# bhi260ap.net
KiCad netlist of a schematic drawn in Altium Designer
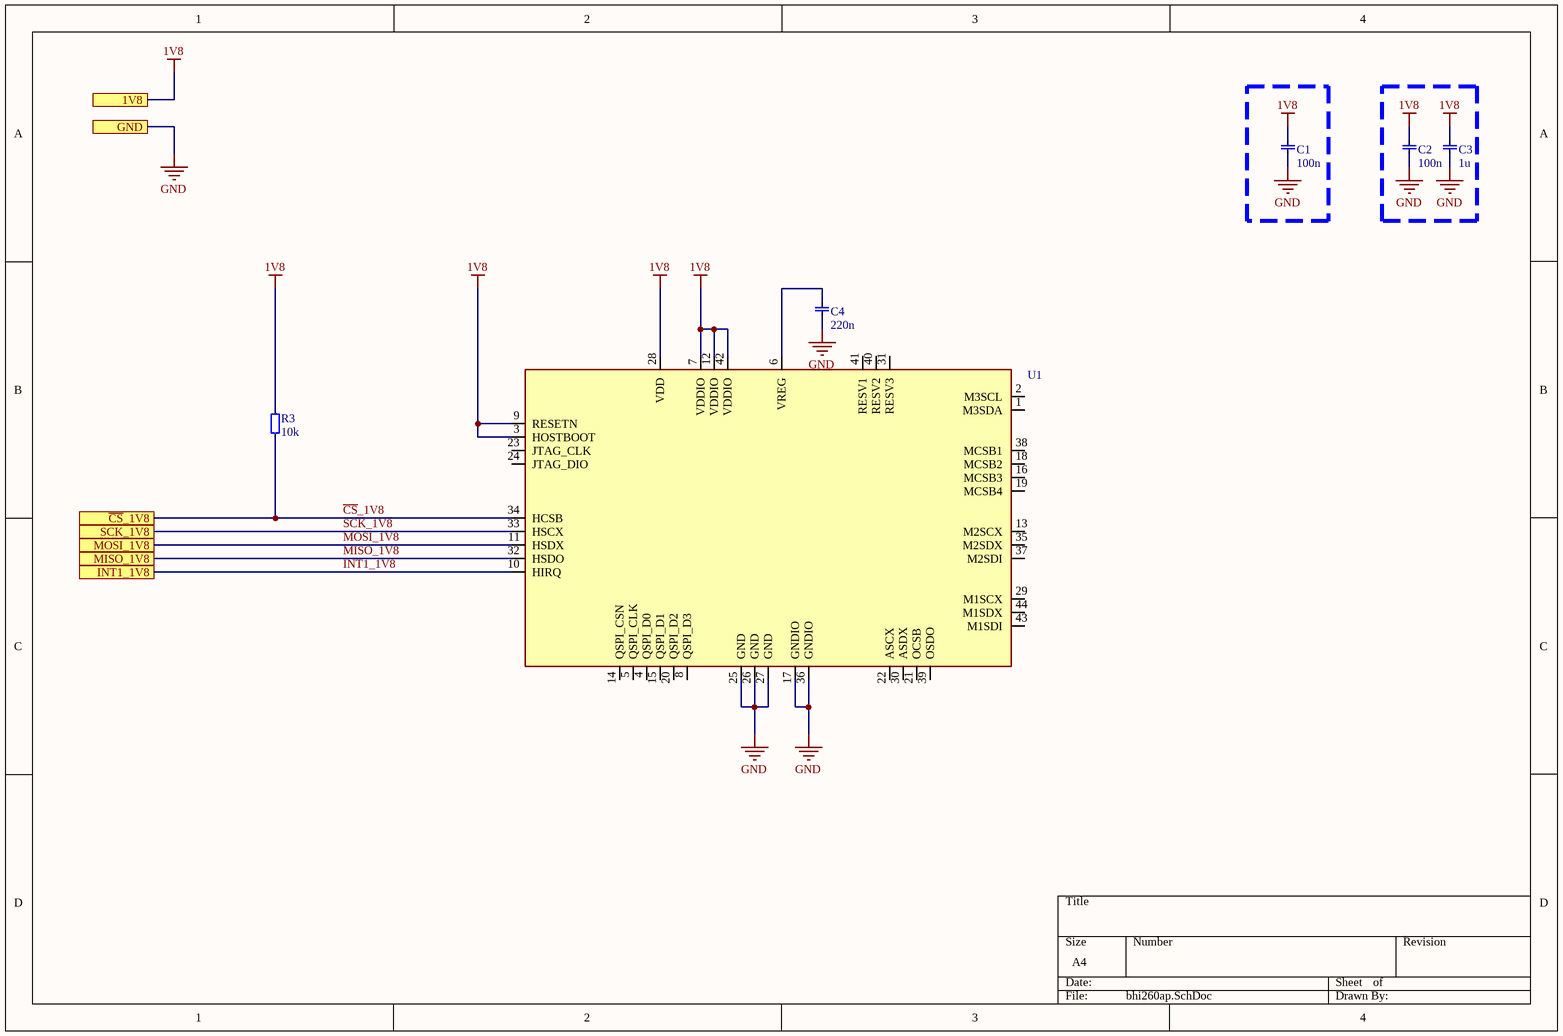
[diagram p0: bhi260ap.SchDoc]

(export (version "E")
  (design (tool "Eeschema 10.0.6"))
  (components
    (comp (ref "C1")
      (value "100n")
      (footprint "0402 CAP")
      (fields (field (name "Comment") "0402 capacitor"))
      (libsource (lib "jclib") (part "0402 capacitor"))
    )
    (comp (ref "C2")
      (value "100n")
      (footprint "0402 CAP")
      (fields (field (name "Comment") "0402 capacitor"))
      (libsource (lib "jclib") (part "0402 capacitor"))
    )
    (comp (ref "C3")
      (value "1u")
      (footprint "0402 CAP")
      (fields (field (name "Comment") "0402 capacitor"))
      (libsource (lib "jclib") (part "0402 capacitor"))
    )
    (comp (ref "C4")
      (value "220n")
      (footprint "0402 CAP")
      (fields (field (name "Comment") "0402 capacitor"))
      (libsource (lib "jclib") (part "0402 capacitor"))
    )
    (comp (ref "R3")
      (value "10k")
      (footprint "0402 res")
      (fields (field (name "Comment") "0402, resistor"))
      (libsource (lib "jclib") (part "0402, resistor"))
    )
    (comp (ref "U1")
      (value "BHI260AP")
      (footprint "44-LGA")
      (description "Self-learning AI smart sensor with integrated IMU")
      (libsource (lib "jclib") (part "BHI260AP"))
    )
  )
  (nets
    (net (code "1") (name "/INT1_1V8") (class "Default")
      (node (ref "U1") (pin "10") (pinfunction "HIRQ_10") (pintype "passive"))
    )
    (net (code "2") (name "/MISO_1V8") (class "Default")
      (node (ref "U1") (pin "32") (pinfunction "HSDO_32") (pintype "passive"))
    )
    (net (code "3") (name "/MOSI_1V8") (class "Default")
      (node (ref "U1") (pin "11") (pinfunction "HSDX_11") (pintype "passive"))
    )
    (net (code "4") (name "/SCK_1V8") (class "Default")
      (node (ref "U1") (pin "33") (pinfunction "HSCX_33") (pintype "passive"))
    )
    (net (code "5") (name "/~{CS}_1V8") (class "Default")
      (node (ref "R3") (pin "1") (pinfunction "1_1") (pintype "passive"))
      (node (ref "U1") (pin "34") (pinfunction "HCSB_34") (pintype "passive"))
    )
    (net (code "6") (name "1V8") (class "Default")
      (node (ref "C1") (pin "1") (pinfunction "1_1") (pintype "passive"))
      (node (ref "C2") (pin "1") (pinfunction "1_1") (pintype "passive"))
      (node (ref "C3") (pin "1") (pinfunction "1_1") (pintype "passive"))
      (node (ref "R3") (pin "0") (pinfunction "0_0") (pintype "passive"))
      (node (ref "U1") (pin "12") (pinfunction "VDDIO_12") (pintype "passive"))
      (node (ref "U1") (pin "28") (pinfunction "VDD_28") (pintype "passive"))
      (node (ref "U1") (pin "3") (pinfunction "HOSTBOOT_3") (pintype "passive"))
      (node (ref "U1") (pin "42") (pinfunction "VDDIO_42") (pintype "passive"))
      (node (ref "U1") (pin "7") (pinfunction "VDDIO_7") (pintype "passive"))
      (node (ref "U1") (pin "9") (pinfunction "RESETN_9") (pintype "passive"))
    )
    (net (code "7") (name "GND") (class "Default")
      (node (ref "C1") (pin "0") (pinfunction "0_0") (pintype "passive"))
      (node (ref "C2") (pin "0") (pinfunction "0_0") (pintype "passive"))
      (node (ref "C3") (pin "0") (pinfunction "0_0") (pintype "passive"))
      (node (ref "C4") (pin "0") (pinfunction "0_0") (pintype "passive"))
      (node (ref "U1") (pin "17") (pinfunction "GNDIO_17") (pintype "passive"))
      (node (ref "U1") (pin "25") (pinfunction "GND_25") (pintype "passive"))
      (node (ref "U1") (pin "26") (pinfunction "GND_26") (pintype "passive"))
      (node (ref "U1") (pin "27") (pinfunction "GND_27") (pintype "passive"))
      (node (ref "U1") (pin "36") (pinfunction "GNDIO_36") (pintype "passive"))
    )
    (net (code "8") (name "Net-(U1-VREG)") (class "Default")
      (node (ref "C4") (pin "1") (pinfunction "1_1") (pintype "passive"))
      (node (ref "U1") (pin "6") (pinfunction "VREG_6") (pintype "passive"))
    )
    (net (code "9") (name "unconnected-(U1-ASCX-Pad22)") (class "Default")
      (node (ref "U1") (pin "22") (pinfunction "ASCX_22") (pintype "passive"))
    )
    (net (code "10") (name "unconnected-(U1-ASDX-Pad30)") (class "Default")
      (node (ref "U1") (pin "30") (pinfunction "ASDX_30") (pintype "passive"))
    )
    (net (code "11") (name "unconnected-(U1-JTAG_CLK-Pad23)") (class "Default")
      (node (ref "U1") (pin "23") (pinfunction "JTAG_CLK_23") (pintype "passive"))
    )
    (net (code "12") (name "unconnected-(U1-JTAG_DIO-Pad24)") (class "Default")
      (node (ref "U1") (pin "24") (pinfunction "JTAG_DIO_24") (pintype "passive"))
    )
    (net (code "13") (name "unconnected-(U1-M1SCX-Pad29)") (class "Default")
      (node (ref "U1") (pin "29") (pinfunction "M1SCX_29") (pintype "passive"))
    )
    (net (code "14") (name "unconnected-(U1-M1SDI-Pad43)") (class "Default")
      (node (ref "U1") (pin "43") (pinfunction "M1SDI_43") (pintype "passive"))
    )
    (net (code "15") (name "unconnected-(U1-M1SDX-Pad44)") (class "Default")
      (node (ref "U1") (pin "44") (pinfunction "M1SDX_44") (pintype "passive"))
    )
    (net (code "16") (name "unconnected-(U1-M2SCX-Pad13)") (class "Default")
      (node (ref "U1") (pin "13") (pinfunction "M2SCX_13") (pintype "passive"))
    )
    (net (code "17") (name "unconnected-(U1-M2SDI-Pad37)") (class "Default")
      (node (ref "U1") (pin "37") (pinfunction "M2SDI_37") (pintype "passive"))
    )
    (net (code "18") (name "unconnected-(U1-M2SDX-Pad35)") (class "Default")
      (node (ref "U1") (pin "35") (pinfunction "M2SDX_35") (pintype "passive"))
    )
    (net (code "19") (name "unconnected-(U1-M3SCL-Pad2)") (class "Default")
      (node (ref "U1") (pin "2") (pinfunction "M3SCL_2") (pintype "passive"))
    )
    (net (code "20") (name "unconnected-(U1-M3SDA-Pad1)") (class "Default")
      (node (ref "U1") (pin "1") (pinfunction "M3SDA_1") (pintype "passive"))
    )
    (net (code "21") (name "unconnected-(U1-MCSB1-Pad38)") (class "Default")
      (node (ref "U1") (pin "38") (pinfunction "MCSB1_38") (pintype "passive"))
    )
    (net (code "22") (name "unconnected-(U1-MCSB2-Pad18)") (class "Default")
      (node (ref "U1") (pin "18") (pinfunction "MCSB2_18") (pintype "passive"))
    )
    (net (code "23") (name "unconnected-(U1-MCSB3-Pad16)") (class "Default")
      (node (ref "U1") (pin "16") (pinfunction "MCSB3_16") (pintype "passive"))
    )
    (net (code "24") (name "unconnected-(U1-MCSB4-Pad19)") (class "Default")
      (node (ref "U1") (pin "19") (pinfunction "MCSB4_19") (pintype "passive"))
    )
    (net (code "25") (name "unconnected-(U1-OCSB-Pad21)") (class "Default")
      (node (ref "U1") (pin "21") (pinfunction "OCSB_21") (pintype "passive"))
    )
    (net (code "26") (name "unconnected-(U1-OSDO-Pad39)") (class "Default")
      (node (ref "U1") (pin "39") (pinfunction "OSDO_39") (pintype "passive"))
    )
    (net (code "27") (name "unconnected-(U1-QSPI_CLK-Pad5)") (class "Default")
      (node (ref "U1") (pin "5") (pinfunction "QSPI_CLK_5") (pintype "passive"))
    )
    (net (code "28") (name "unconnected-(U1-QSPI_CSN-Pad14)") (class "Default")
      (node (ref "U1") (pin "14") (pinfunction "QSPI_CSN_14") (pintype "passive"))
    )
    (net (code "29") (name "unconnected-(U1-QSPI_D0-Pad4)") (class "Default")
      (node (ref "U1") (pin "4") (pinfunction "QSPI_D0_4") (pintype "passive"))
    )
    (net (code "30") (name "unconnected-(U1-QSPI_D1-Pad15)") (class "Default")
      (node (ref "U1") (pin "15") (pinfunction "QSPI_D1_15") (pintype "passive"))
    )
    (net (code "31") (name "unconnected-(U1-QSPI_D2-Pad20)") (class "Default")
      (node (ref "U1") (pin "20") (pinfunction "QSPI_D2_20") (pintype "passive"))
    )
    (net (code "32") (name "unconnected-(U1-QSPI_D3-Pad8)") (class "Default")
      (node (ref "U1") (pin "8") (pinfunction "QSPI_D3_8") (pintype "passive"))
    )
    (net (code "33") (name "unconnected-(U1-RESV1-Pad41)") (class "Default")
      (node (ref "U1") (pin "41") (pinfunction "RESV1_41") (pintype "passive"))
    )
    (net (code "34") (name "unconnected-(U1-RESV2-Pad40)") (class "Default")
      (node (ref "U1") (pin "40") (pinfunction "RESV2_40") (pintype "passive"))
    )
    (net (code "35") (name "unconnected-(U1-RESV3-Pad31)") (class "Default")
      (node (ref "U1") (pin "31") (pinfunction "RESV3_31") (pintype "passive"))
    )
  )
)
